# IceWerx_Carrier_Enzo_Florendo.net
KiCad netlist of a schematic drawn in EAGLE
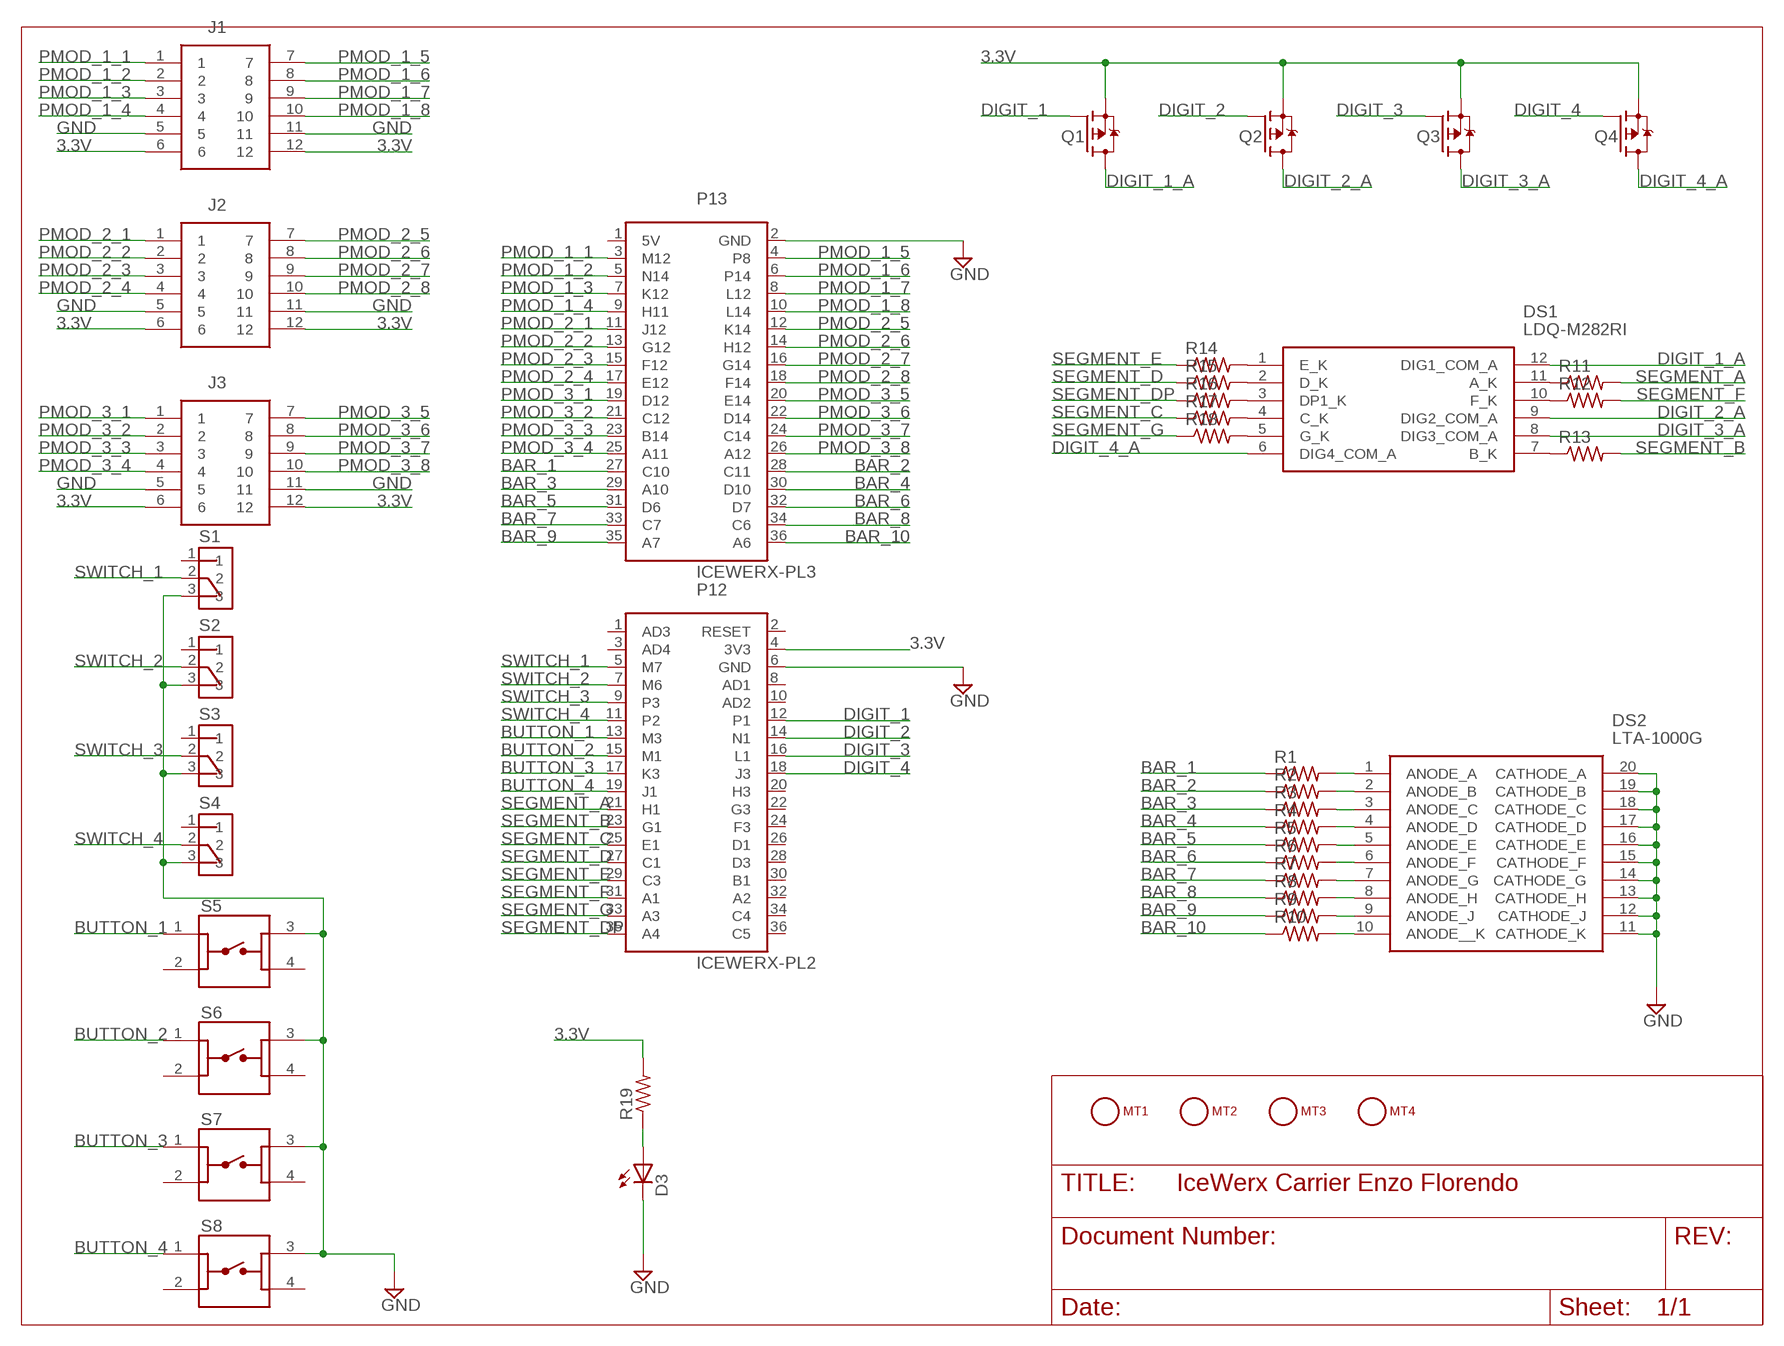
[diagram p0: schematic, sheet 1]

(export (version "E")
  (design (tool "Eeschema 10.0.6"))
  (components
    (comp (ref "D3")
      (value "LED5MM")
      (footprint "eagle-import:LED5MM")
      (libsource (lib "eagle-import") (part "LED5MM"))
    )
    (comp (ref "DS1")
      (value "LDQ-M282RI")
      (footprint "eagle-import:LDQM282RI")
      (fields (field (name "MOUSER_PART_NUMBER") "696-LDQ-M282RI"))
      (libsource (lib "eagle-import") (part "LDQ-M282RI"))
    )
    (comp (ref "DS2")
      (value "LTA-1000G")
      (footprint "eagle-import:DIPS762W50P254L2527H825Q20N")
      (fields (field (name "MOUSER_PART_NUMBER") "859-LTA-1000G"))
      (libsource (lib "eagle-import") (part "LTA-1000G"))
    )
    (comp (ref "J1")
      (value "PMOD-SOCKET-FOR-HOST-BOARD")
      (footprint "eagle-import:PMOD-SOCKET-FOR-HOST-BOARD")
      (libsource (lib "eagle-import") (part "PMOD-SOCKET-FOR-HOST-BOARD"))
    )
    (comp (ref "J2")
      (value "PMOD-SOCKET-FOR-HOST-BOARD")
      (footprint "eagle-import:PMOD-SOCKET-FOR-HOST-BOARD")
      (libsource (lib "eagle-import") (part "PMOD-SOCKET-FOR-HOST-BOARD"))
    )
    (comp (ref "J3")
      (value "PMOD-SOCKET-FOR-HOST-BOARD")
      (footprint "eagle-import:PMOD-SOCKET-FOR-HOST-BOARD")
      (libsource (lib "eagle-import") (part "PMOD-SOCKET-FOR-HOST-BOARD"))
    )
    (comp (ref "MT1")
      (value "MOUNTING_HOLE-125_250_ROUND")
      (footprint "eagle-import:MT_125_250")
      (libsource (lib "eagle-import") (part "MOUNTING_HOLE-125_250_ROUND"))
    )
    (comp (ref "MT2")
      (value "MOUNTING_HOLE-125_250_ROUND")
      (footprint "eagle-import:MT_125_250")
      (libsource (lib "eagle-import") (part "MOUNTING_HOLE-125_250_ROUND"))
    )
    (comp (ref "MT3")
      (value "MOUNTING_HOLE-125_250_ROUND")
      (footprint "eagle-import:MT_125_250")
      (libsource (lib "eagle-import") (part "MOUNTING_HOLE-125_250_ROUND"))
    )
    (comp (ref "MT4")
      (value "MOUNTING_HOLE-125_250_ROUND")
      (footprint "eagle-import:MT_125_250")
      (libsource (lib "eagle-import") (part "MOUNTING_HOLE-125_250_ROUND"))
    )
    (comp (ref "P12")
      (value "ICEWERX-PL2")
      (footprint "eagle-import:TE_4-1734506-1")
      (libsource (lib "eagle-import") (part "ICEWERX-PL2"))
    )
    (comp (ref "P13")
      (value "ICEWERX-PL3")
      (footprint "eagle-import:TE_4-1734506-1")
      (libsource (lib "eagle-import") (part "ICEWERX-PL3"))
    )
    (comp (ref "Q1")
      (value "NX2301P")
      (footprint "eagle-import:SOT95P230X110-3N")
      (fields (field (name "MANUFACTURER") "Nexperia"))
      (libsource (lib "eagle-import") (part "NX2301P"))
    )
    (comp (ref "Q2")
      (value "NX2301P")
      (footprint "eagle-import:SOT95P230X110-3N")
      (fields (field (name "MANUFACTURER") "Nexperia"))
      (libsource (lib "eagle-import") (part "NX2301P"))
    )
    (comp (ref "Q3")
      (value "NX2301P")
      (footprint "eagle-import:SOT95P230X110-3N")
      (fields (field (name "MANUFACTURER") "Nexperia"))
      (libsource (lib "eagle-import") (part "NX2301P"))
    )
    (comp (ref "Q4")
      (value "NX2301P")
      (footprint "eagle-import:SOT95P230X110-3N")
      (fields (field (name "MANUFACTURER") "Nexperia"))
      (libsource (lib "eagle-import") (part "NX2301P"))
    )
    (comp (ref "R1")
      (value "R-US_0204/5")
      (footprint "eagle-import:0204_5")
      (libsource (lib "eagle-import") (part "R-US_0204/5"))
    )
    (comp (ref "R2")
      (value "R-US_0204/5")
      (footprint "eagle-import:0204_5")
      (libsource (lib "eagle-import") (part "R-US_0204/5"))
    )
    (comp (ref "R3")
      (value "R-US_0204/5")
      (footprint "eagle-import:0204_5")
      (libsource (lib "eagle-import") (part "R-US_0204/5"))
    )
    (comp (ref "R4")
      (value "R-US_0204/5")
      (footprint "eagle-import:0204_5")
      (libsource (lib "eagle-import") (part "R-US_0204/5"))
    )
    (comp (ref "R5")
      (value "R-US_0204/5")
      (footprint "eagle-import:0204_5")
      (libsource (lib "eagle-import") (part "R-US_0204/5"))
    )
    (comp (ref "R6")
      (value "R-US_0204/5")
      (footprint "eagle-import:0204_5")
      (libsource (lib "eagle-import") (part "R-US_0204/5"))
    )
    (comp (ref "R7")
      (value "R-US_0204/5")
      (footprint "eagle-import:0204_5")
      (libsource (lib "eagle-import") (part "R-US_0204/5"))
    )
    (comp (ref "R8")
      (value "R-US_0204/5")
      (footprint "eagle-import:0204_5")
      (libsource (lib "eagle-import") (part "R-US_0204/5"))
    )
    (comp (ref "R9")
      (value "R-US_0204/5")
      (footprint "eagle-import:0204_5")
      (libsource (lib "eagle-import") (part "R-US_0204/5"))
    )
    (comp (ref "R10")
      (value "R-US_0204/5")
      (footprint "eagle-import:0204_5")
      (libsource (lib "eagle-import") (part "R-US_0204/5"))
    )
    (comp (ref "R11")
      (value "R-US_0204/5")
      (footprint "eagle-import:0204_5")
      (libsource (lib "eagle-import") (part "R-US_0204/5"))
    )
    (comp (ref "R12")
      (value "R-US_0204/5")
      (footprint "eagle-import:0204_5")
      (libsource (lib "eagle-import") (part "R-US_0204/5"))
    )
    (comp (ref "R13")
      (value "R-US_0204/5")
      (footprint "eagle-import:0204_5")
      (libsource (lib "eagle-import") (part "R-US_0204/5"))
    )
    (comp (ref "R14")
      (value "R-US_0204/5")
      (footprint "eagle-import:0204_5")
      (libsource (lib "eagle-import") (part "R-US_0204/5"))
    )
    (comp (ref "R15")
      (value "R-US_0204/5")
      (footprint "eagle-import:0204_5")
      (libsource (lib "eagle-import") (part "R-US_0204/5"))
    )
    (comp (ref "R16")
      (value "R-US_0204/5")
      (footprint "eagle-import:0204_5")
      (libsource (lib "eagle-import") (part "R-US_0204/5"))
    )
    (comp (ref "R17")
      (value "R-US_0204/5")
      (footprint "eagle-import:0204_5")
      (libsource (lib "eagle-import") (part "R-US_0204/5"))
    )
    (comp (ref "R18")
      (value "R-US_0204/5")
      (footprint "eagle-import:0204_5")
      (libsource (lib "eagle-import") (part "R-US_0204/5"))
    )
    (comp (ref "R19")
      (value "R-US_0204/5")
      (footprint "eagle-import:0204_5")
      (libsource (lib "eagle-import") (part "R-US_0204/5"))
    )
    (comp (ref "S1")
      (value "OS102011MS2QN1")
      (footprint "eagle-import:SW_OS102011MS2QN1")
      (fields (field (name "MANUFACTURER") "C&K"))
      (libsource (lib "eagle-import") (part "OS102011MS2QN1"))
    )
    (comp (ref "S2")
      (value "OS102011MS2QN1")
      (footprint "eagle-import:SW_OS102011MS2QN1")
      (fields (field (name "MANUFACTURER") "C&K"))
      (libsource (lib "eagle-import") (part "OS102011MS2QN1"))
    )
    (comp (ref "S3")
      (value "OS102011MS2QN1")
      (footprint "eagle-import:SW_OS102011MS2QN1")
      (fields (field (name "MANUFACTURER") "C&K"))
      (libsource (lib "eagle-import") (part "OS102011MS2QN1"))
    )
    (comp (ref "S4")
      (value "OS102011MS2QN1")
      (footprint "eagle-import:SW_OS102011MS2QN1")
      (fields (field (name "MANUFACTURER") "C&K"))
      (libsource (lib "eagle-import") (part "OS102011MS2QN1"))
    )
    (comp (ref "S5")
      (value "1825910-7")
      (footprint "eagle-import:SW_1825910-7")
      (fields (field (name "MANUFACTURER") "TE Connectivity"))
      (libsource (lib "eagle-import") (part "1825910-7"))
    )
    (comp (ref "S6")
      (value "1825910-7")
      (footprint "eagle-import:SW_1825910-7")
      (fields (field (name "MANUFACTURER") "TE Connectivity"))
      (libsource (lib "eagle-import") (part "1825910-7"))
    )
    (comp (ref "S7")
      (value "1825910-7")
      (footprint "eagle-import:SW_1825910-7")
      (fields (field (name "MANUFACTURER") "TE Connectivity"))
      (libsource (lib "eagle-import") (part "1825910-7"))
    )
    (comp (ref "S8")
      (value "1825910-7")
      (footprint "eagle-import:SW_1825910-7")
      (fields (field (name "MANUFACTURER") "TE Connectivity"))
      (libsource (lib "eagle-import") (part "1825910-7"))
    )
  )
  (nets
    (net (code "1") (name "/3.3V") (class "Default")
      (node (ref "J1") (pin "12") (pinfunction "12_12") (pintype "bidirectional"))
      (node (ref "J1") (pin "6") (pinfunction "6_6") (pintype "bidirectional"))
      (node (ref "J2") (pin "12") (pinfunction "12_12") (pintype "bidirectional"))
      (node (ref "J2") (pin "6") (pinfunction "6_6") (pintype "bidirectional"))
      (node (ref "J3") (pin "12") (pinfunction "12_12") (pintype "bidirectional"))
      (node (ref "J3") (pin "6") (pinfunction "6_6") (pintype "bidirectional"))
      (node (ref "P12") (pin "4") (pinfunction "3V3_4") (pintype "bidirectional"))
      (node (ref "Q1") (pin "2") (pinfunction "S_2") (pintype "passive"))
      (node (ref "Q2") (pin "2") (pinfunction "S_2") (pintype "passive"))
      (node (ref "Q3") (pin "2") (pinfunction "S_2") (pintype "passive"))
      (node (ref "Q4") (pin "2") (pinfunction "S_2") (pintype "passive"))
      (node (ref "R19") (pin "2") (pinfunction "2_2") (pintype "passive"))
    )
    (net (code "2") (name "/BAR_1") (class "Default")
      (node (ref "P13") (pin "27") (pinfunction "C10_27") (pintype "bidirectional"))
      (node (ref "R1") (pin "1") (pinfunction "1_1") (pintype "passive"))
    )
    (net (code "3") (name "/BAR_2") (class "Default")
      (node (ref "P13") (pin "28") (pinfunction "C11_28") (pintype "bidirectional"))
      (node (ref "R2") (pin "1") (pinfunction "1_1") (pintype "passive"))
    )
    (net (code "4") (name "/BAR_3") (class "Default")
      (node (ref "P13") (pin "29") (pinfunction "A10_29") (pintype "bidirectional"))
      (node (ref "R3") (pin "1") (pinfunction "1_1") (pintype "passive"))
    )
    (net (code "5") (name "/BAR_4") (class "Default")
      (node (ref "P13") (pin "30") (pinfunction "D10_30") (pintype "bidirectional"))
      (node (ref "R4") (pin "1") (pinfunction "1_1") (pintype "passive"))
    )
    (net (code "6") (name "/BAR_5") (class "Default")
      (node (ref "P13") (pin "31") (pinfunction "D6_31") (pintype "bidirectional"))
      (node (ref "R5") (pin "1") (pinfunction "1_1") (pintype "passive"))
    )
    (net (code "7") (name "/BAR_6") (class "Default")
      (node (ref "P13") (pin "32") (pinfunction "D7_32") (pintype "bidirectional"))
      (node (ref "R6") (pin "1") (pinfunction "1_1") (pintype "passive"))
    )
    (net (code "8") (name "/BAR_7") (class "Default")
      (node (ref "P13") (pin "33") (pinfunction "C7_33") (pintype "bidirectional"))
      (node (ref "R7") (pin "1") (pinfunction "1_1") (pintype "passive"))
    )
    (net (code "9") (name "/BAR_8") (class "Default")
      (node (ref "P13") (pin "34") (pinfunction "C6_34") (pintype "bidirectional"))
      (node (ref "R8") (pin "1") (pinfunction "1_1") (pintype "passive"))
    )
    (net (code "10") (name "/BAR_9") (class "Default")
      (node (ref "P13") (pin "35") (pinfunction "A7_35") (pintype "bidirectional"))
      (node (ref "R9") (pin "1") (pinfunction "1_1") (pintype "passive"))
    )
    (net (code "11") (name "/BAR_10") (class "Default")
      (node (ref "P13") (pin "36") (pinfunction "A6_36") (pintype "bidirectional"))
      (node (ref "R10") (pin "1") (pinfunction "1_1") (pintype "passive"))
    )
    (net (code "12") (name "/BUTTON_1") (class "Default")
      (node (ref "P12") (pin "13") (pinfunction "M3_13") (pintype "bidirectional"))
      (node (ref "S5") (pin "1") (pinfunction "1_1") (pintype "passive"))
    )
    (net (code "13") (name "/BUTTON_2") (class "Default")
      (node (ref "P12") (pin "15") (pinfunction "M1_15") (pintype "bidirectional"))
      (node (ref "S6") (pin "1") (pinfunction "1_1") (pintype "passive"))
    )
    (net (code "14") (name "/BUTTON_3") (class "Default")
      (node (ref "P12") (pin "17") (pinfunction "K3_17") (pintype "bidirectional"))
      (node (ref "S7") (pin "1") (pinfunction "1_1") (pintype "passive"))
    )
    (net (code "15") (name "/BUTTON_4") (class "Default")
      (node (ref "P12") (pin "19") (pinfunction "J1_19") (pintype "bidirectional"))
      (node (ref "S8") (pin "1") (pinfunction "1_1") (pintype "passive"))
    )
    (net (code "16") (name "/DIGIT_1") (class "Default")
      (node (ref "P12") (pin "12") (pinfunction "P1_12") (pintype "bidirectional"))
      (node (ref "Q1") (pin "1") (pinfunction "G_1") (pintype "passive"))
    )
    (net (code "17") (name "/DIGIT_1_A") (class "Default")
      (node (ref "DS1") (pin "12") (pinfunction "DIG1_COM_A_12") (pintype "bidirectional"))
      (node (ref "Q1") (pin "3") (pinfunction "D_3") (pintype "passive"))
    )
    (net (code "18") (name "/DIGIT_2") (class "Default")
      (node (ref "P12") (pin "14") (pinfunction "N1_14") (pintype "bidirectional"))
      (node (ref "Q2") (pin "1") (pinfunction "G_1") (pintype "passive"))
    )
    (net (code "19") (name "/DIGIT_2_A") (class "Default")
      (node (ref "DS1") (pin "9") (pinfunction "DIG2_COM_A_9") (pintype "bidirectional"))
      (node (ref "Q2") (pin "3") (pinfunction "D_3") (pintype "passive"))
    )
    (net (code "20") (name "/DIGIT_3") (class "Default")
      (node (ref "P12") (pin "16") (pinfunction "L1_16") (pintype "bidirectional"))
      (node (ref "Q3") (pin "1") (pinfunction "G_1") (pintype "passive"))
    )
    (net (code "21") (name "/DIGIT_3_A") (class "Default")
      (node (ref "DS1") (pin "8") (pinfunction "DIG3_COM_A_8") (pintype "bidirectional"))
      (node (ref "Q3") (pin "3") (pinfunction "D_3") (pintype "passive"))
    )
    (net (code "22") (name "/DIGIT_4") (class "Default")
      (node (ref "P12") (pin "18") (pinfunction "J3_18") (pintype "bidirectional"))
      (node (ref "Q4") (pin "1") (pinfunction "G_1") (pintype "passive"))
    )
    (net (code "23") (name "/DIGIT_4_A") (class "Default")
      (node (ref "DS1") (pin "6") (pinfunction "DIG4_COM_A_6") (pintype "bidirectional"))
      (node (ref "Q4") (pin "3") (pinfunction "D_3") (pintype "passive"))
    )
    (net (code "24") (name "/PMOD_1_1") (class "Default")
      (node (ref "J1") (pin "1") (pinfunction "1_1") (pintype "bidirectional"))
      (node (ref "P13") (pin "3") (pinfunction "M12_3") (pintype "bidirectional"))
    )
    (net (code "25") (name "/PMOD_1_2") (class "Default")
      (node (ref "J1") (pin "2") (pinfunction "2_2") (pintype "bidirectional"))
      (node (ref "P13") (pin "5") (pinfunction "N14_5") (pintype "bidirectional"))
    )
    (net (code "26") (name "/PMOD_1_3") (class "Default")
      (node (ref "J1") (pin "3") (pinfunction "3_3") (pintype "bidirectional"))
      (node (ref "P13") (pin "7") (pinfunction "K12_7") (pintype "bidirectional"))
    )
    (net (code "27") (name "/PMOD_1_4") (class "Default")
      (node (ref "J1") (pin "4") (pinfunction "4_4") (pintype "bidirectional"))
      (node (ref "P13") (pin "9") (pinfunction "H11_9") (pintype "bidirectional"))
    )
    (net (code "28") (name "/PMOD_1_5") (class "Default")
      (node (ref "J1") (pin "7") (pinfunction "7_7") (pintype "bidirectional"))
      (node (ref "P13") (pin "4") (pinfunction "P8_4") (pintype "bidirectional"))
    )
    (net (code "29") (name "/PMOD_1_6") (class "Default")
      (node (ref "J1") (pin "8") (pinfunction "8_8") (pintype "bidirectional"))
      (node (ref "P13") (pin "6") (pinfunction "P14_6") (pintype "bidirectional"))
    )
    (net (code "30") (name "/PMOD_1_7") (class "Default")
      (node (ref "J1") (pin "9") (pinfunction "9_9") (pintype "bidirectional"))
      (node (ref "P13") (pin "8") (pinfunction "L12_8") (pintype "bidirectional"))
    )
    (net (code "31") (name "/PMOD_1_8") (class "Default")
      (node (ref "J1") (pin "10") (pinfunction "10_10") (pintype "bidirectional"))
      (node (ref "P13") (pin "10") (pinfunction "L14_10") (pintype "bidirectional"))
    )
    (net (code "32") (name "/PMOD_2_1") (class "Default")
      (node (ref "J2") (pin "1") (pinfunction "1_1") (pintype "bidirectional"))
      (node (ref "P13") (pin "11") (pinfunction "J12_11") (pintype "bidirectional"))
    )
    (net (code "33") (name "/PMOD_2_2") (class "Default")
      (node (ref "J2") (pin "2") (pinfunction "2_2") (pintype "bidirectional"))
      (node (ref "P13") (pin "13") (pinfunction "G12_13") (pintype "bidirectional"))
    )
    (net (code "34") (name "/PMOD_2_3") (class "Default")
      (node (ref "J2") (pin "3") (pinfunction "3_3") (pintype "bidirectional"))
      (node (ref "P13") (pin "15") (pinfunction "F12_15") (pintype "bidirectional"))
    )
    (net (code "35") (name "/PMOD_2_4") (class "Default")
      (node (ref "J2") (pin "4") (pinfunction "4_4") (pintype "bidirectional"))
      (node (ref "P13") (pin "17") (pinfunction "E12_17") (pintype "bidirectional"))
    )
    (net (code "36") (name "/PMOD_2_5") (class "Default")
      (node (ref "J2") (pin "7") (pinfunction "7_7") (pintype "bidirectional"))
      (node (ref "P13") (pin "12") (pinfunction "K14_12") (pintype "bidirectional"))
    )
    (net (code "37") (name "/PMOD_2_6") (class "Default")
      (node (ref "J2") (pin "8") (pinfunction "8_8") (pintype "bidirectional"))
      (node (ref "P13") (pin "14") (pinfunction "H12_14") (pintype "bidirectional"))
    )
    (net (code "38") (name "/PMOD_2_7") (class "Default")
      (node (ref "J2") (pin "9") (pinfunction "9_9") (pintype "bidirectional"))
      (node (ref "P13") (pin "16") (pinfunction "G14_16") (pintype "bidirectional"))
    )
    (net (code "39") (name "/PMOD_2_8") (class "Default")
      (node (ref "J2") (pin "10") (pinfunction "10_10") (pintype "bidirectional"))
      (node (ref "P13") (pin "18") (pinfunction "F14_18") (pintype "bidirectional"))
    )
    (net (code "40") (name "/PMOD_3_1") (class "Default")
      (node (ref "J3") (pin "1") (pinfunction "1_1") (pintype "bidirectional"))
      (node (ref "P13") (pin "19") (pinfunction "D12_19") (pintype "bidirectional"))
    )
    (net (code "41") (name "/PMOD_3_2") (class "Default")
      (node (ref "J3") (pin "2") (pinfunction "2_2") (pintype "bidirectional"))
      (node (ref "P13") (pin "21") (pinfunction "C12_21") (pintype "bidirectional"))
    )
    (net (code "42") (name "/PMOD_3_3") (class "Default")
      (node (ref "J3") (pin "3") (pinfunction "3_3") (pintype "bidirectional"))
      (node (ref "P13") (pin "23") (pinfunction "B14_23") (pintype "bidirectional"))
    )
    (net (code "43") (name "/PMOD_3_4") (class "Default")
      (node (ref "J3") (pin "4") (pinfunction "4_4") (pintype "bidirectional"))
      (node (ref "P13") (pin "25") (pinfunction "A11_25") (pintype "bidirectional"))
    )
    (net (code "44") (name "/PMOD_3_5") (class "Default")
      (node (ref "J3") (pin "7") (pinfunction "7_7") (pintype "bidirectional"))
      (node (ref "P13") (pin "20") (pinfunction "E14_20") (pintype "bidirectional"))
    )
    (net (code "45") (name "/PMOD_3_6") (class "Default")
      (node (ref "J3") (pin "8") (pinfunction "8_8") (pintype "bidirectional"))
      (node (ref "P13") (pin "22") (pinfunction "D14_22") (pintype "bidirectional"))
    )
    (net (code "46") (name "/PMOD_3_7") (class "Default")
      (node (ref "J3") (pin "9") (pinfunction "9_9") (pintype "bidirectional"))
      (node (ref "P13") (pin "24") (pinfunction "C14_24") (pintype "bidirectional"))
    )
    (net (code "47") (name "/PMOD_3_8") (class "Default")
      (node (ref "J3") (pin "10") (pinfunction "10_10") (pintype "bidirectional"))
      (node (ref "P13") (pin "26") (pinfunction "A12_26") (pintype "bidirectional"))
    )
    (net (code "48") (name "/SEGMENT_A") (class "Default")
      (node (ref "P12") (pin "21") (pinfunction "H1_21") (pintype "bidirectional"))
      (node (ref "R11") (pin "2") (pinfunction "2_2") (pintype "passive"))
    )
    (net (code "49") (name "/SEGMENT_B") (class "Default")
      (node (ref "P12") (pin "23") (pinfunction "G1_23") (pintype "bidirectional"))
      (node (ref "R13") (pin "2") (pinfunction "2_2") (pintype "passive"))
    )
    (net (code "50") (name "/SEGMENT_C") (class "Default")
      (node (ref "P12") (pin "25") (pinfunction "E1_25") (pintype "bidirectional"))
      (node (ref "R17") (pin "1") (pinfunction "1_1") (pintype "passive"))
    )
    (net (code "51") (name "/SEGMENT_D") (class "Default")
      (node (ref "P12") (pin "27") (pinfunction "C1_27") (pintype "bidirectional"))
      (node (ref "R15") (pin "1") (pinfunction "1_1") (pintype "passive"))
    )
    (net (code "52") (name "/SEGMENT_DP") (class "Default")
      (node (ref "P12") (pin "35") (pinfunction "A4_35") (pintype "bidirectional"))
      (node (ref "R16") (pin "1") (pinfunction "1_1") (pintype "passive"))
    )
    (net (code "53") (name "/SEGMENT_E") (class "Default")
      (node (ref "P12") (pin "29") (pinfunction "C3_29") (pintype "bidirectional"))
      (node (ref "R14") (pin "1") (pinfunction "1_1") (pintype "passive"))
    )
    (net (code "54") (name "/SEGMENT_F") (class "Default")
      (node (ref "P12") (pin "31") (pinfunction "A1_31") (pintype "bidirectional"))
      (node (ref "R12") (pin "2") (pinfunction "2_2") (pintype "passive"))
    )
    (net (code "55") (name "/SEGMENT_G") (class "Default")
      (node (ref "P12") (pin "33") (pinfunction "A3_33") (pintype "bidirectional"))
      (node (ref "R18") (pin "1") (pinfunction "1_1") (pintype "passive"))
    )
    (net (code "56") (name "/SWITCH_1") (class "Default")
      (node (ref "P12") (pin "5") (pinfunction "M7_5") (pintype "bidirectional"))
      (node (ref "S1") (pin "2") (pinfunction "2_2") (pintype "passive"))
    )
    (net (code "57") (name "/SWITCH_2") (class "Default")
      (node (ref "P12") (pin "7") (pinfunction "M6_7") (pintype "bidirectional"))
      (node (ref "S2") (pin "2") (pinfunction "2_2") (pintype "passive"))
    )
    (net (code "58") (name "/SWITCH_3") (class "Default")
      (node (ref "P12") (pin "9") (pinfunction "P3_9") (pintype "bidirectional"))
      (node (ref "S3") (pin "2") (pinfunction "2_2") (pintype "passive"))
    )
    (net (code "59") (name "/SWITCH_4") (class "Default")
      (node (ref "P12") (pin "11") (pinfunction "P2_11") (pintype "bidirectional"))
      (node (ref "S4") (pin "2") (pinfunction "2_2") (pintype "passive"))
    )
    (net (code "60") (name "GND") (class "Default")
      (node (ref "D3") (pin "K") (pinfunction "C_K") (pintype "passive"))
      (node (ref "DS2") (pin "11") (pinfunction "CATHODE_K_11") (pintype "bidirectional"))
      (node (ref "DS2") (pin "12") (pinfunction "CATHODE_J_12") (pintype "bidirectional"))
      (node (ref "DS2") (pin "13") (pinfunction "CATHODE_H_13") (pintype "bidirectional"))
      (node (ref "DS2") (pin "14") (pinfunction "CATHODE_G_14") (pintype "bidirectional"))
      (node (ref "DS2") (pin "15") (pinfunction "CATHODE_F_15") (pintype "bidirectional"))
      (node (ref "DS2") (pin "16") (pinfunction "CATHODE_E_16") (pintype "bidirectional"))
      (node (ref "DS2") (pin "17") (pinfunction "CATHODE_D_17") (pintype "bidirectional"))
      (node (ref "DS2") (pin "18") (pinfunction "CATHODE_C_18") (pintype "bidirectional"))
      (node (ref "DS2") (pin "19") (pinfunction "CATHODE_B_19") (pintype "bidirectional"))
      (node (ref "DS2") (pin "20") (pinfunction "CATHODE_A_20") (pintype "bidirectional"))
      (node (ref "J1") (pin "11") (pinfunction "11_11") (pintype "bidirectional"))
      (node (ref "J1") (pin "5") (pinfunction "5_5") (pintype "bidirectional"))
      (node (ref "J2") (pin "11") (pinfunction "11_11") (pintype "bidirectional"))
      (node (ref "J2") (pin "5") (pinfunction "5_5") (pintype "bidirectional"))
      (node (ref "J3") (pin "11") (pinfunction "11_11") (pintype "bidirectional"))
      (node (ref "J3") (pin "5") (pinfunction "5_5") (pintype "bidirectional"))
      (node (ref "P12") (pin "6") (pinfunction "GND_6") (pintype "bidirectional"))
      (node (ref "P13") (pin "2") (pinfunction "GND_2") (pintype "bidirectional"))
      (node (ref "S1") (pin "3") (pinfunction "3_3") (pintype "passive"))
      (node (ref "S2") (pin "3") (pinfunction "3_3") (pintype "passive"))
      (node (ref "S3") (pin "3") (pinfunction "3_3") (pintype "passive"))
      (node (ref "S4") (pin "3") (pinfunction "3_3") (pintype "passive"))
      (node (ref "S5") (pin "3") (pinfunction "3_3") (pintype "passive"))
      (node (ref "S6") (pin "3") (pinfunction "3_3") (pintype "passive"))
      (node (ref "S7") (pin "3") (pinfunction "3_3") (pintype "passive"))
      (node (ref "S8") (pin "3") (pinfunction "3_3") (pintype "passive"))
    )
    (net (code "61") (name "Net-(D3-PadA)") (class "Default")
      (node (ref "D3") (pin "A") (pinfunction "A_A") (pintype "passive"))
      (node (ref "R19") (pin "1") (pinfunction "1_1") (pintype "passive"))
    )
    (net (code "62") (name "Net-(DS1-A_K)") (class "Default")
      (node (ref "DS1") (pin "11") (pinfunction "A_K_11") (pintype "bidirectional"))
      (node (ref "R11") (pin "1") (pinfunction "1_1") (pintype "passive"))
    )
    (net (code "63") (name "Net-(DS1-B_K)") (class "Default")
      (node (ref "DS1") (pin "7") (pinfunction "B_K_7") (pintype "bidirectional"))
      (node (ref "R13") (pin "1") (pinfunction "1_1") (pintype "passive"))
    )
    (net (code "64") (name "Net-(DS1-C_K)") (class "Default")
      (node (ref "DS1") (pin "4") (pinfunction "C_K_4") (pintype "bidirectional"))
      (node (ref "R17") (pin "2") (pinfunction "2_2") (pintype "passive"))
    )
    (net (code "65") (name "Net-(DS1-DP1_K)") (class "Default")
      (node (ref "DS1") (pin "3") (pinfunction "DP1_K_3") (pintype "bidirectional"))
      (node (ref "R16") (pin "2") (pinfunction "2_2") (pintype "passive"))
    )
    (net (code "66") (name "Net-(DS1-D_K)") (class "Default")
      (node (ref "DS1") (pin "2") (pinfunction "D_K_2") (pintype "bidirectional"))
      (node (ref "R15") (pin "2") (pinfunction "2_2") (pintype "passive"))
    )
    (net (code "67") (name "Net-(DS1-E_K)") (class "Default")
      (node (ref "DS1") (pin "1") (pinfunction "E_K_1") (pintype "bidirectional"))
      (node (ref "R14") (pin "2") (pinfunction "2_2") (pintype "passive"))
    )
    (net (code "68") (name "Net-(DS1-F_K)") (class "Default")
      (node (ref "DS1") (pin "10") (pinfunction "F_K_10") (pintype "bidirectional"))
      (node (ref "R12") (pin "1") (pinfunction "1_1") (pintype "passive"))
    )
    (net (code "69") (name "Net-(DS1-G_K)") (class "Default")
      (node (ref "DS1") (pin "5") (pinfunction "G_K_5") (pintype "bidirectional"))
      (node (ref "R18") (pin "2") (pinfunction "2_2") (pintype "passive"))
    )
    (net (code "70") (name "Net-(DS2-ANODE_A)") (class "Default")
      (node (ref "DS2") (pin "1") (pinfunction "ANODE_A_1") (pintype "bidirectional"))
      (node (ref "R1") (pin "2") (pinfunction "2_2") (pintype "passive"))
    )
    (net (code "71") (name "Net-(DS2-ANODE_B)") (class "Default")
      (node (ref "DS2") (pin "2") (pinfunction "ANODE_B_2") (pintype "bidirectional"))
      (node (ref "R2") (pin "2") (pinfunction "2_2") (pintype "passive"))
    )
    (net (code "72") (name "Net-(DS2-ANODE_C)") (class "Default")
      (node (ref "DS2") (pin "3") (pinfunction "ANODE_C_3") (pintype "bidirectional"))
      (node (ref "R3") (pin "2") (pinfunction "2_2") (pintype "passive"))
    )
    (net (code "73") (name "Net-(DS2-ANODE_D)") (class "Default")
      (node (ref "DS2") (pin "4") (pinfunction "ANODE_D_4") (pintype "bidirectional"))
      (node (ref "R4") (pin "2") (pinfunction "2_2") (pintype "passive"))
    )
    (net (code "74") (name "Net-(DS2-ANODE_E)") (class "Default")
      (node (ref "DS2") (pin "5") (pinfunction "ANODE_E_5") (pintype "bidirectional"))
      (node (ref "R5") (pin "2") (pinfunction "2_2") (pintype "passive"))
    )
    (net (code "75") (name "Net-(DS2-ANODE_F)") (class "Default")
      (node (ref "DS2") (pin "6") (pinfunction "ANODE_F_6") (pintype "bidirectional"))
      (node (ref "R6") (pin "2") (pinfunction "2_2") (pintype "passive"))
    )
    (net (code "76") (name "Net-(DS2-ANODE_G)") (class "Default")
      (node (ref "DS2") (pin "7") (pinfunction "ANODE_G_7") (pintype "bidirectional"))
      (node (ref "R7") (pin "2") (pinfunction "2_2") (pintype "passive"))
    )
    (net (code "77") (name "Net-(DS2-ANODE_H)") (class "Default")
      (node (ref "DS2") (pin "8") (pinfunction "ANODE_H_8") (pintype "bidirectional"))
      (node (ref "R8") (pin "2") (pinfunction "2_2") (pintype "passive"))
    )
    (net (code "78") (name "Net-(DS2-ANODE_J)") (class "Default")
      (node (ref "DS2") (pin "9") (pinfunction "ANODE_J_9") (pintype "bidirectional"))
      (node (ref "R9") (pin "2") (pinfunction "2_2") (pintype "passive"))
    )
    (net (code "79") (name "Net-(DS2-ANODE__K)") (class "Default")
      (node (ref "DS2") (pin "10") (pinfunction "ANODE__K_10") (pintype "bidirectional"))
      (node (ref "R10") (pin "2") (pinfunction "2_2") (pintype "passive"))
    )
    (net (code "80") (name "unconnected-(MT1-P$1-Pad1)") (class "Default")
      (node (ref "MT1") (pin "1") (pinfunction "P$1_1") (pintype "bidirectional"))
    )
    (net (code "81") (name "unconnected-(MT2-P$1-Pad1)") (class "Default")
      (node (ref "MT2") (pin "1") (pinfunction "P$1_1") (pintype "bidirectional"))
    )
    (net (code "82") (name "unconnected-(MT3-P$1-Pad1)") (class "Default")
      (node (ref "MT3") (pin "1") (pinfunction "P$1_1") (pintype "bidirectional"))
    )
    (net (code "83") (name "unconnected-(MT4-P$1-Pad1)") (class "Default")
      (node (ref "MT4") (pin "1") (pinfunction "P$1_1") (pintype "bidirectional"))
    )
    (net (code "84") (name "unconnected-(P12-A2-Pad32)") (class "Default")
      (node (ref "P12") (pin "32") (pinfunction "A2_32") (pintype "bidirectional"))
    )
    (net (code "85") (name "unconnected-(P12-AD1-Pad8)") (class "Default")
      (node (ref "P12") (pin "8") (pinfunction "AD1_8") (pintype "bidirectional"))
    )
    (net (code "86") (name "unconnected-(P12-AD2-Pad10)") (class "Default")
      (node (ref "P12") (pin "10") (pinfunction "AD2_10") (pintype "bidirectional"))
    )
    (net (code "87") (name "unconnected-(P12-AD3-Pad1)") (class "Default")
      (node (ref "P12") (pin "1") (pinfunction "AD3_1") (pintype "bidirectional"))
    )
    (net (code "88") (name "unconnected-(P12-AD4-Pad3)") (class "Default")
      (node (ref "P12") (pin "3") (pinfunction "AD4_3") (pintype "bidirectional"))
    )
    (net (code "89") (name "unconnected-(P12-B1-Pad30)") (class "Default")
      (node (ref "P12") (pin "30") (pinfunction "B1_30") (pintype "bidirectional"))
    )
    (net (code "90") (name "unconnected-(P12-C4-Pad34)") (class "Default")
      (node (ref "P12") (pin "34") (pinfunction "C4_34") (pintype "bidirectional"))
    )
    (net (code "91") (name "unconnected-(P12-C5-Pad36)") (class "Default")
      (node (ref "P12") (pin "36") (pinfunction "C5_36") (pintype "bidirectional"))
    )
    (net (code "92") (name "unconnected-(P12-D1-Pad26)") (class "Default")
      (node (ref "P12") (pin "26") (pinfunction "D1_26") (pintype "bidirectional"))
    )
    (net (code "93") (name "unconnected-(P12-D3-Pad28)") (class "Default")
      (node (ref "P12") (pin "28") (pinfunction "D3_28") (pintype "bidirectional"))
    )
    (net (code "94") (name "unconnected-(P12-F3-Pad24)") (class "Default")
      (node (ref "P12") (pin "24") (pinfunction "F3_24") (pintype "bidirectional"))
    )
    (net (code "95") (name "unconnected-(P12-G3-Pad22)") (class "Default")
      (node (ref "P12") (pin "22") (pinfunction "G3_22") (pintype "bidirectional"))
    )
    (net (code "96") (name "unconnected-(P12-H3-Pad20)") (class "Default")
      (node (ref "P12") (pin "20") (pinfunction "H3_20") (pintype "bidirectional"))
    )
    (net (code "97") (name "unconnected-(P12-RESET-Pad2)") (class "Default")
      (node (ref "P12") (pin "2") (pinfunction "RESET_2") (pintype "bidirectional"))
    )
    (net (code "98") (name "unconnected-(P13-5V-Pad1)") (class "Default")
      (node (ref "P13") (pin "1") (pinfunction "5V_1") (pintype "bidirectional"))
    )
    (net (code "99") (name "unconnected-(S1-Pad1)") (class "Default")
      (node (ref "S1") (pin "1") (pinfunction "1_1") (pintype "passive"))
    )
    (net (code "100") (name "unconnected-(S2-Pad1)") (class "Default")
      (node (ref "S2") (pin "1") (pinfunction "1_1") (pintype "passive"))
    )
    (net (code "101") (name "unconnected-(S3-Pad1)") (class "Default")
      (node (ref "S3") (pin "1") (pinfunction "1_1") (pintype "passive"))
    )
    (net (code "102") (name "unconnected-(S4-Pad1)") (class "Default")
      (node (ref "S4") (pin "1") (pinfunction "1_1") (pintype "passive"))
    )
    (net (code "103") (name "unconnected-(S5-Pad2)") (class "Default")
      (node (ref "S5") (pin "2") (pinfunction "2_2") (pintype "passive"))
    )
    (net (code "104") (name "unconnected-(S5-Pad4)") (class "Default")
      (node (ref "S5") (pin "4") (pinfunction "4_4") (pintype "passive"))
    )
    (net (code "105") (name "unconnected-(S6-Pad2)") (class "Default")
      (node (ref "S6") (pin "2") (pinfunction "2_2") (pintype "passive"))
    )
    (net (code "106") (name "unconnected-(S6-Pad4)") (class "Default")
      (node (ref "S6") (pin "4") (pinfunction "4_4") (pintype "passive"))
    )
    (net (code "107") (name "unconnected-(S7-Pad2)") (class "Default")
      (node (ref "S7") (pin "2") (pinfunction "2_2") (pintype "passive"))
    )
    (net (code "108") (name "unconnected-(S7-Pad4)") (class "Default")
      (node (ref "S7") (pin "4") (pinfunction "4_4") (pintype "passive"))
    )
    (net (code "109") (name "unconnected-(S8-Pad2)") (class "Default")
      (node (ref "S8") (pin "2") (pinfunction "2_2") (pintype "passive"))
    )
    (net (code "110") (name "unconnected-(S8-Pad4)") (class "Default")
      (node (ref "S8") (pin "4") (pinfunction "4_4") (pintype "passive"))
    )
  )
)
